# sw63_mk3_jig.net
KiCad netlist of a schematic drawn in EAGLE
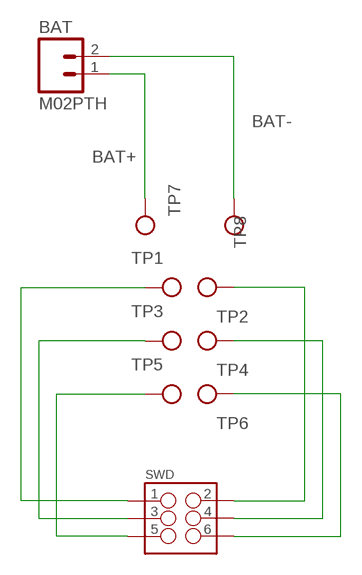
[diagram p0: schematic, sheet 1]

(export (version "E")
  (design (tool "Eeschema 10.0.6"))
  (components
    (comp (ref "BAT")
      (value "M02PTH")
      (footprint "eagle-import:1X02")
      (libsource (lib "eagle-import") (part "M02PTH"))
    )
    (comp (ref "SWD")
      (value "M03X2POGO_ROUND")
      (footprint "eagle-import:2X3_POGO_ROUND")
      (libsource (lib "eagle-import") (part "M03X2POGO_ROUND"))
    )
    (comp (ref "TP1")
      (value "R-075-SC")
      (footprint "eagle-import:R-075")
      (libsource (lib "eagle-import") (part "R-075-SC"))
    )
    (comp (ref "TP2")
      (value "R-075-SC")
      (footprint "eagle-import:R-075")
      (libsource (lib "eagle-import") (part "R-075-SC"))
    )
    (comp (ref "TP3")
      (value "R-075-SC")
      (footprint "eagle-import:R-075")
      (libsource (lib "eagle-import") (part "R-075-SC"))
    )
    (comp (ref "TP4")
      (value "R-075-SC")
      (footprint "eagle-import:R-075")
      (libsource (lib "eagle-import") (part "R-075-SC"))
    )
    (comp (ref "TP5")
      (value "R-075-SC")
      (footprint "eagle-import:R-075")
      (libsource (lib "eagle-import") (part "R-075-SC"))
    )
    (comp (ref "TP6")
      (value "R-075-SC")
      (footprint "eagle-import:R-075")
      (libsource (lib "eagle-import") (part "R-075-SC"))
    )
    (comp (ref "TP7")
      (value "R-075-SC")
      (footprint "eagle-import:R-075")
      (libsource (lib "eagle-import") (part "R-075-SC"))
    )
    (comp (ref "TP8")
      (value "R-075-SC")
      (footprint "eagle-import:R-075")
      (libsource (lib "eagle-import") (part "R-075-SC"))
    )
  )
  (nets
    (net (code "1") (name "/BAT+") (class "Default")
      (node (ref "BAT") (pin "1") (pinfunction "1_1") (pintype "passive"))
      (node (ref "TP7") (pin "P$1") (pinfunction "P$1_P$1") (pintype "bidirectional"))
    )
    (net (code "2") (name "/BAT-") (class "Default")
      (node (ref "BAT") (pin "2") (pinfunction "2_2") (pintype "passive"))
      (node (ref "TP8") (pin "P$1") (pinfunction "P$1_P$1") (pintype "bidirectional"))
    )
    (net (code "3") (name "Net-(SWD-1)") (class "Default")
      (node (ref "SWD") (pin "P$1") (pinfunction "1_P$1") (pintype "bidirectional"))
      (node (ref "TP1") (pin "P$1") (pinfunction "P$1_P$1") (pintype "bidirectional"))
    )
    (net (code "4") (name "Net-(SWD-2)") (class "Default")
      (node (ref "SWD") (pin "P$2") (pinfunction "2_P$2") (pintype "bidirectional"))
      (node (ref "TP2") (pin "P$1") (pinfunction "P$1_P$1") (pintype "bidirectional"))
    )
    (net (code "5") (name "Net-(SWD-3)") (class "Default")
      (node (ref "SWD") (pin "P$3") (pinfunction "3_P$3") (pintype "bidirectional"))
      (node (ref "TP3") (pin "P$1") (pinfunction "P$1_P$1") (pintype "bidirectional"))
    )
    (net (code "6") (name "Net-(SWD-4)") (class "Default")
      (node (ref "SWD") (pin "P$4") (pinfunction "4_P$4") (pintype "bidirectional"))
      (node (ref "TP4") (pin "P$1") (pinfunction "P$1_P$1") (pintype "bidirectional"))
    )
    (net (code "7") (name "Net-(SWD-5)") (class "Default")
      (node (ref "SWD") (pin "P$5") (pinfunction "5_P$5") (pintype "bidirectional"))
      (node (ref "TP5") (pin "P$1") (pinfunction "P$1_P$1") (pintype "bidirectional"))
    )
    (net (code "8") (name "Net-(SWD-6)") (class "Default")
      (node (ref "SWD") (pin "P$6") (pinfunction "6_P$6") (pintype "bidirectional"))
      (node (ref "TP6") (pin "P$1") (pinfunction "P$1_P$1") (pintype "bidirectional"))
    )
  )
)
